# mixer_board_smd.net
KiCad netlist of a schematic drawn in EAGLE
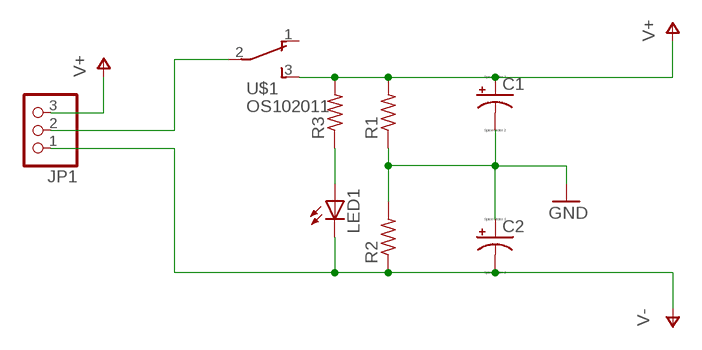
[diagram p0: schematic, sheet 1, part 1 of 2]
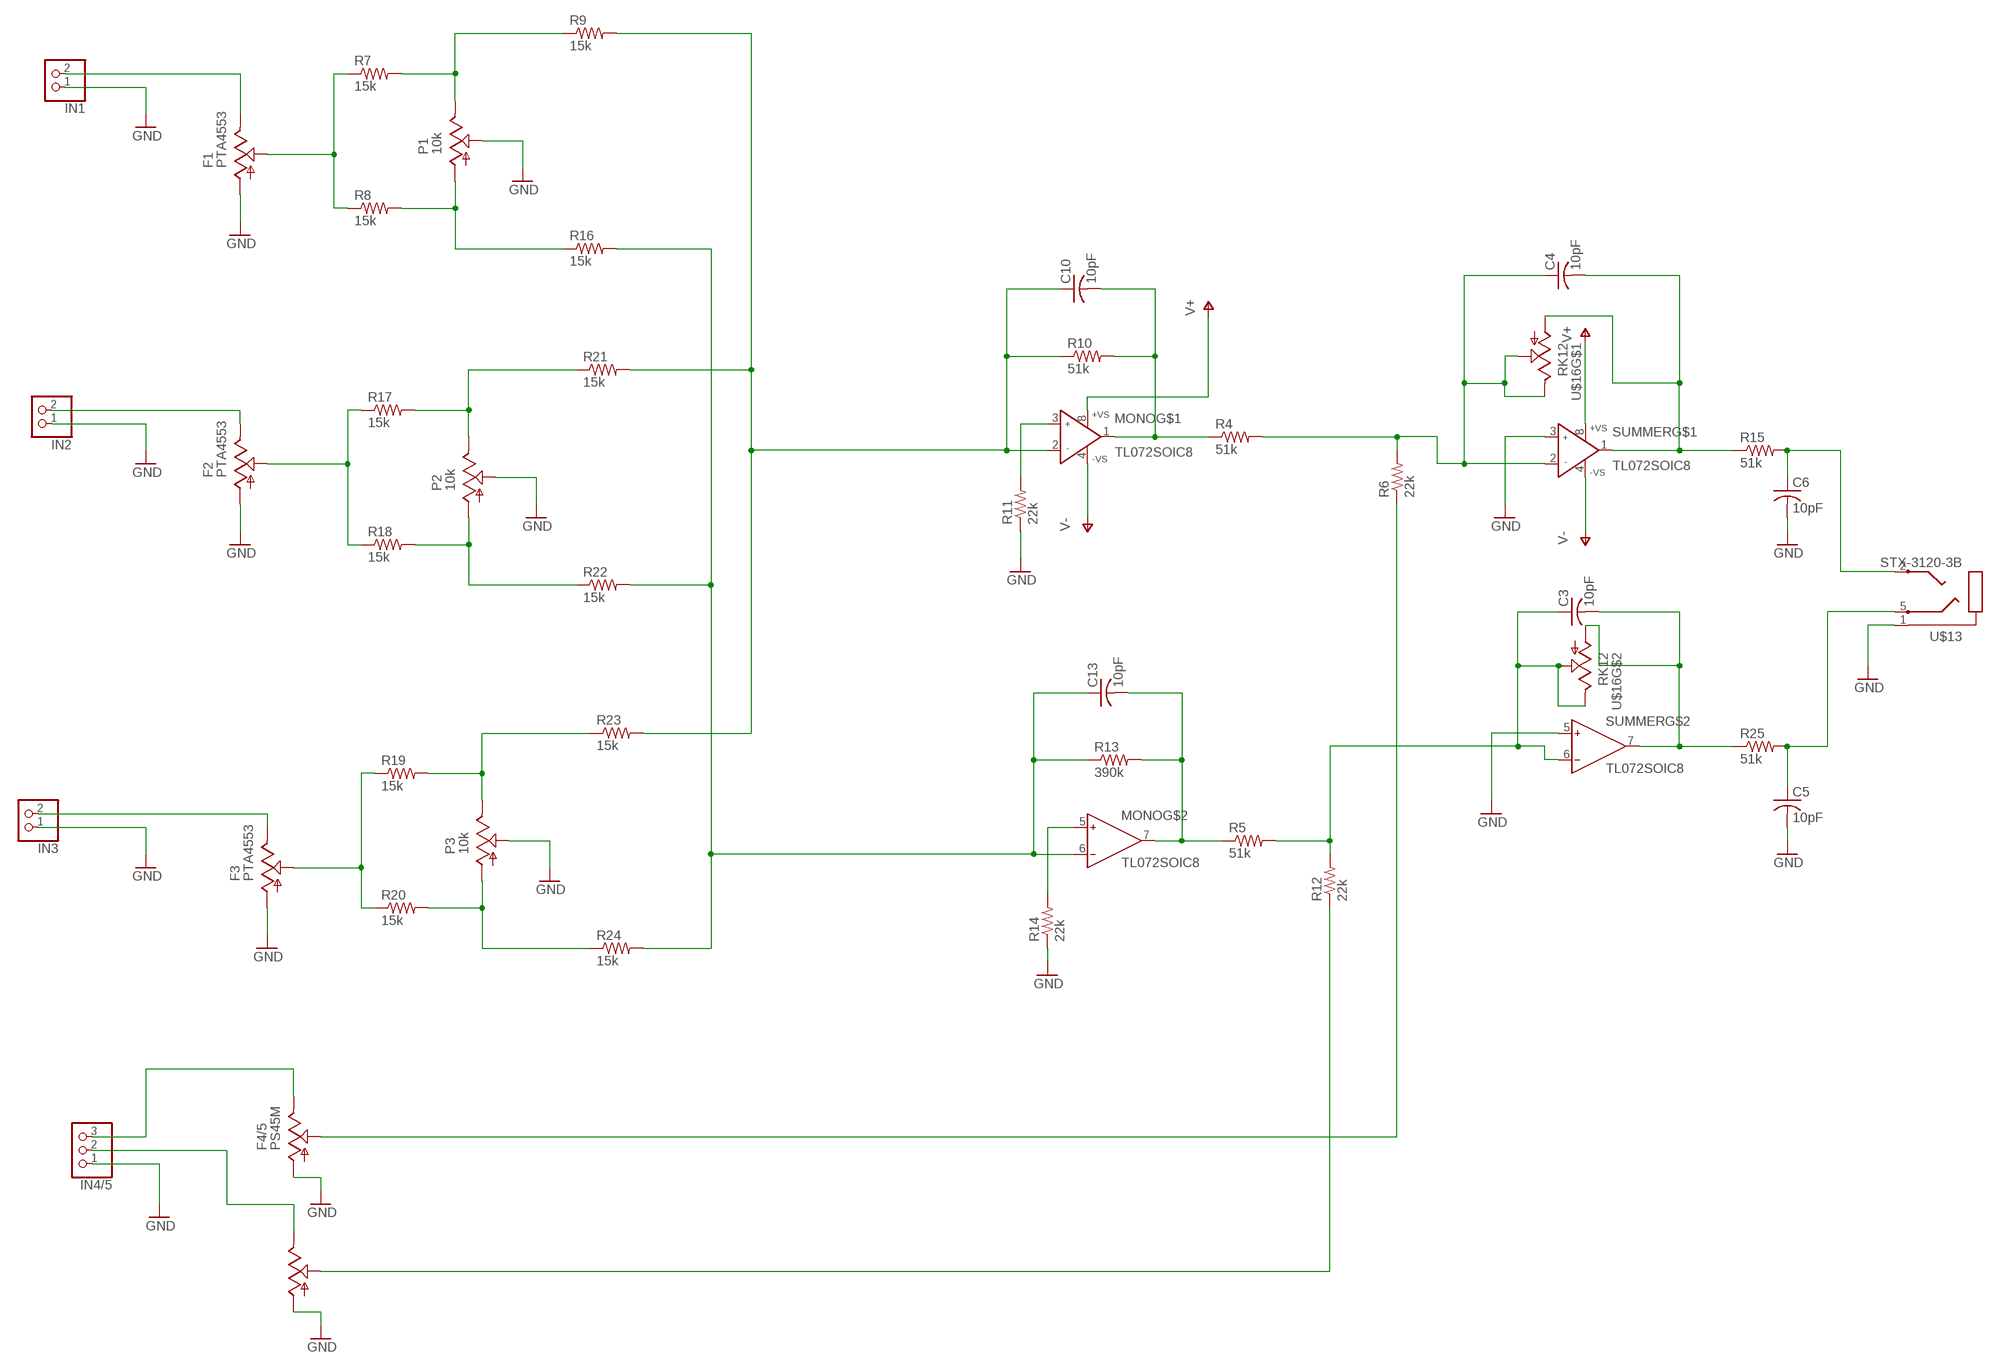
[diagram p1: schematic, sheet 1, part 2 of 2]

(export (version "E")
  (design (tool "Eeschema 10.0.6"))
  (components
    (comp (ref "C1")
      (value "CPOL-USE1.8-4")
      (footprint "eagle-import:E1,8-4")
      (libsource (lib "eagle-import") (part "CPOL-USE1.8-4"))
    )
    (comp (ref "C2")
      (value "CPOL-USE1.8-4")
      (footprint "eagle-import:E1,8-4")
      (libsource (lib "eagle-import") (part "CPOL-USE1.8-4"))
    )
    (comp (ref "C3")
      (value "10pF")
      (footprint "eagle-import:C0805")
      (libsource (lib "eagle-import") (part "C-USC0805"))
    )
    (comp (ref "C4")
      (value "10pF")
      (footprint "eagle-import:C0805")
      (libsource (lib "eagle-import") (part "C-USC0805"))
    )
    (comp (ref "C5")
      (value "10pF")
      (footprint "eagle-import:C0805")
      (libsource (lib "eagle-import") (part "C-USC0805"))
    )
    (comp (ref "C6")
      (value "10pF")
      (footprint "eagle-import:C0805")
      (libsource (lib "eagle-import") (part "C-USC0805"))
    )
    (comp (ref "C10")
      (value "10pF")
      (footprint "eagle-import:C0805")
      (libsource (lib "eagle-import") (part "C-USC0805"))
    )
    (comp (ref "C13")
      (value "10pF")
      (footprint "eagle-import:C0805")
      (libsource (lib "eagle-import") (part "C-USC0805"))
    )
    (comp (ref "F1")
      (value "PTA4553")
      (footprint "eagle-import:PTA4553")
      (libsource (lib "eagle-import") (part "PTA4553"))
    )
    (comp (ref "F2")
      (value "PTA4553")
      (footprint "eagle-import:PTA4553")
      (libsource (lib "eagle-import") (part "PTA4553"))
    )
    (comp (ref "F3")
      (value "PTA4553")
      (footprint "eagle-import:PTA4553")
      (libsource (lib "eagle-import") (part "PTA4553"))
    )
    (comp (ref "F4/5")
      (value "PS45M")
      (footprint "eagle-import:PS45M")
      (libsource (lib "eagle-import") (part "PS45M"))
    )
    (comp (ref "IN1")
      (value "PINHD-1X2/90")
      (footprint "eagle-import:1X02_90")
      (libsource (lib "eagle-import") (part "PINHD-1X2/90"))
    )
    (comp (ref "IN2")
      (value "PINHD-1X2/90")
      (footprint "eagle-import:1X02_90")
      (libsource (lib "eagle-import") (part "PINHD-1X2/90"))
    )
    (comp (ref "IN3")
      (value "PINHD-1X2/90")
      (footprint "eagle-import:1X02_90")
      (libsource (lib "eagle-import") (part "PINHD-1X2/90"))
    )
    (comp (ref "IN4/5")
      (value "PINHD-1X3/90")
      (footprint "eagle-import:1X03_90")
      (libsource (lib "eagle-import") (part "PINHD-1X3/90"))
    )
    (comp (ref "JP1")
      (value "PINHD-1X3/90")
      (footprint "eagle-import:1X03_90")
      (libsource (lib "eagle-import") (part "PINHD-1X3/90"))
    )
    (comp (ref "LED1")
      (value "LEDCHIPLED_1206")
      (footprint "eagle-import:CHIPLED_1206")
      (libsource (lib "eagle-import") (part "LEDCHIPLED_1206"))
    )
    (comp (ref "MONO")
      (value "TL072SOIC8")
      (footprint "eagle-import:SOIC8")
      (libsource (lib "eagle-import") (part "TL072SOIC8"))
    )
    (comp (ref "P1")
      (value "10k")
      (footprint "eagle-import:PTV09A")
      (libsource (lib "eagle-import") (part "PTV09A"))
    )
    (comp (ref "P2")
      (value "10k")
      (footprint "eagle-import:PTV09A")
      (libsource (lib "eagle-import") (part "PTV09A"))
    )
    (comp (ref "P3")
      (value "10k")
      (footprint "eagle-import:PTV09A")
      (libsource (lib "eagle-import") (part "PTV09A"))
    )
    (comp (ref "R1")
      (value "R-US_M0805")
      (footprint "eagle-import:M0805")
      (libsource (lib "eagle-import") (part "R-US_M0805"))
    )
    (comp (ref "R2")
      (value "R-US_M0805")
      (footprint "eagle-import:M0805")
      (libsource (lib "eagle-import") (part "R-US_M0805"))
    )
    (comp (ref "R3")
      (value "R-US_R0805")
      (footprint "eagle-import:R0805")
      (libsource (lib "eagle-import") (part "R-US_R0805"))
    )
    (comp (ref "R4")
      (value "51k")
      (footprint "eagle-import:M0805")
      (libsource (lib "eagle-import") (part "R-US_M0805"))
    )
    (comp (ref "R5")
      (value "51k")
      (footprint "eagle-import:M0805")
      (libsource (lib "eagle-import") (part "R-US_M0805"))
    )
    (comp (ref "R6")
      (value "22k")
      (footprint "eagle-import:M0805")
      (libsource (lib "eagle-import") (part "R-US_M0805"))
    )
    (comp (ref "R7")
      (value "15k")
      (footprint "eagle-import:M0805")
      (libsource (lib "eagle-import") (part "R-US_M0805"))
    )
    (comp (ref "R8")
      (value "15k")
      (footprint "eagle-import:M0805")
      (libsource (lib "eagle-import") (part "R-US_M0805"))
    )
    (comp (ref "R9")
      (value "15k")
      (footprint "eagle-import:M0805")
      (libsource (lib "eagle-import") (part "R-US_M0805"))
    )
    (comp (ref "R10")
      (value "51k")
      (footprint "eagle-import:M0805")
      (libsource (lib "eagle-import") (part "R-US_M0805"))
    )
    (comp (ref "R11")
      (value "22k")
      (footprint "eagle-import:M0805")
      (libsource (lib "eagle-import") (part "R-US_M0805"))
    )
    (comp (ref "R12")
      (value "22k")
      (footprint "eagle-import:M0805")
      (libsource (lib "eagle-import") (part "R-US_M0805"))
    )
    (comp (ref "R13")
      (value "390k")
      (footprint "eagle-import:M0805")
      (libsource (lib "eagle-import") (part "R-US_M0805"))
    )
    (comp (ref "R14")
      (value "22k")
      (footprint "eagle-import:M0805")
      (libsource (lib "eagle-import") (part "R-US_M0805"))
    )
    (comp (ref "R15")
      (value "51k")
      (footprint "eagle-import:M0805")
      (libsource (lib "eagle-import") (part "R-US_M0805"))
    )
    (comp (ref "R16")
      (value "15k")
      (footprint "eagle-import:M0805")
      (libsource (lib "eagle-import") (part "R-US_M0805"))
    )
    (comp (ref "R17")
      (value "15k")
      (footprint "eagle-import:M0805")
      (libsource (lib "eagle-import") (part "R-US_M0805"))
    )
    (comp (ref "R18")
      (value "15k")
      (footprint "eagle-import:M0805")
      (libsource (lib "eagle-import") (part "R-US_M0805"))
    )
    (comp (ref "R19")
      (value "15k")
      (footprint "eagle-import:M0805")
      (libsource (lib "eagle-import") (part "R-US_M0805"))
    )
    (comp (ref "R20")
      (value "15k")
      (footprint "eagle-import:M0805")
      (libsource (lib "eagle-import") (part "R-US_M0805"))
    )
    (comp (ref "R21")
      (value "15k")
      (footprint "eagle-import:M0805")
      (libsource (lib "eagle-import") (part "R-US_M0805"))
    )
    (comp (ref "R22")
      (value "15k")
      (footprint "eagle-import:M0805")
      (libsource (lib "eagle-import") (part "R-US_M0805"))
    )
    (comp (ref "R23")
      (value "15k")
      (footprint "eagle-import:M0805")
      (libsource (lib "eagle-import") (part "R-US_M0805"))
    )
    (comp (ref "R24")
      (value "15k")
      (footprint "eagle-import:M0805")
      (libsource (lib "eagle-import") (part "R-US_M0805"))
    )
    (comp (ref "R25")
      (value "51k")
      (footprint "eagle-import:M0805")
      (libsource (lib "eagle-import") (part "R-US_M0805"))
    )
    (comp (ref "SUMMER")
      (value "TL072SOIC8")
      (footprint "eagle-import:SOIC8")
      (libsource (lib "eagle-import") (part "TL072SOIC8"))
    )
    (comp (ref "U$1")
      (value "OS102011")
      (footprint "eagle-import:OS102011")
      (libsource (lib "eagle-import") (part "OS102011"))
    )
    (comp (ref "U$13")
      (value "STX-3120-3B")
      (footprint "eagle-import:STX-3120")
      (libsource (lib "eagle-import") (part "STX-3120-3B"))
    )
    (comp (ref "U$16")
      (value "RK12")
      (footprint "eagle-import:RK12")
      (libsource (lib "eagle-import") (part "RK12"))
    )
  )
  (nets
    (net (code "1") (name "GND") (class "Default")
      (node (ref "C1") (pin "-") (pinfunction "-_-") (pintype "passive"))
      (node (ref "C2") (pin "+") (pinfunction "+_+") (pintype "passive"))
      (node (ref "C5") (pin "2") (pinfunction "2_2") (pintype "passive"))
      (node (ref "C6") (pin "2") (pinfunction "2_2") (pintype "passive"))
      (node (ref "F1") (pin "1") (pinfunction "1_1") (pintype "passive"))
      (node (ref "F2") (pin "1") (pinfunction "1_1") (pintype "passive"))
      (node (ref "F3") (pin "1") (pinfunction "1_1") (pintype "passive"))
      (node (ref "F4/5") (pin "1") (pinfunction "1_1") (pintype "passive"))
      (node (ref "F4/5") (pin "1'") (pinfunction "1'_1'") (pintype "passive"))
      (node (ref "IN1") (pin "1") (pinfunction "1_1") (pintype "passive"))
      (node (ref "IN2") (pin "1") (pinfunction "1_1") (pintype "passive"))
      (node (ref "IN3") (pin "1") (pinfunction "1_1") (pintype "passive"))
      (node (ref "IN4/5") (pin "1") (pinfunction "1_1") (pintype "passive"))
      (node (ref "P1") (pin "2") (pinfunction "2_2") (pintype "passive"))
      (node (ref "P2") (pin "2") (pinfunction "2_2") (pintype "passive"))
      (node (ref "P3") (pin "2") (pinfunction "2_2") (pintype "passive"))
      (node (ref "R1") (pin "1") (pinfunction "1_1") (pintype "passive"))
      (node (ref "R11") (pin "1") (pinfunction "1_1") (pintype "passive"))
      (node (ref "R14") (pin "1") (pinfunction "1_1") (pintype "passive"))
      (node (ref "R2") (pin "2") (pinfunction "2_2") (pintype "passive"))
      (node (ref "SUMMER") (pin "3") (pinfunction "IN+_3") (pintype "input"))
      (node (ref "SUMMER") (pin "5") (pinfunction "IN+_5") (pintype "input"))
      (node (ref "U$13") (pin "1") (pinfunction "1_1") (pintype "passive"))
    )
    (net (code "2") (name "Net-(C5-Pad1)") (class "Default")
      (node (ref "C5") (pin "1") (pinfunction "1_1") (pintype "passive"))
      (node (ref "R25") (pin "2") (pinfunction "2_2") (pintype "passive"))
      (node (ref "U$13") (pin "5") (pinfunction "5_5") (pintype "passive"))
    )
    (net (code "3") (name "Net-(C6-Pad1)") (class "Default")
      (node (ref "C6") (pin "1") (pinfunction "1_1") (pintype "passive"))
      (node (ref "R15") (pin "2") (pinfunction "2_2") (pintype "passive"))
      (node (ref "U$13") (pin "2") (pinfunction "2_2") (pintype "passive"))
    )
    (net (code "4") (name "Net-(F1-Pad2)") (class "Default")
      (node (ref "F1") (pin "2") (pinfunction "2_2") (pintype "passive"))
      (node (ref "R7") (pin "1") (pinfunction "1_1") (pintype "passive"))
      (node (ref "R8") (pin "1") (pinfunction "1_1") (pintype "passive"))
    )
    (net (code "5") (name "Net-(F1-Pad3)") (class "Default")
      (node (ref "F1") (pin "3") (pinfunction "3_3") (pintype "passive"))
      (node (ref "IN1") (pin "2") (pinfunction "2_2") (pintype "passive"))
    )
    (net (code "6") (name "Net-(F2-Pad2)") (class "Default")
      (node (ref "F2") (pin "2") (pinfunction "2_2") (pintype "passive"))
      (node (ref "R17") (pin "1") (pinfunction "1_1") (pintype "passive"))
      (node (ref "R18") (pin "1") (pinfunction "1_1") (pintype "passive"))
    )
    (net (code "7") (name "Net-(F2-Pad3)") (class "Default")
      (node (ref "F2") (pin "3") (pinfunction "3_3") (pintype "passive"))
      (node (ref "IN2") (pin "2") (pinfunction "2_2") (pintype "passive"))
    )
    (net (code "8") (name "Net-(F3-Pad2)") (class "Default")
      (node (ref "F3") (pin "2") (pinfunction "2_2") (pintype "passive"))
      (node (ref "R19") (pin "1") (pinfunction "1_1") (pintype "passive"))
      (node (ref "R20") (pin "1") (pinfunction "1_1") (pintype "passive"))
    )
    (net (code "9") (name "Net-(F3-Pad3)") (class "Default")
      (node (ref "F3") (pin "3") (pinfunction "3_3") (pintype "passive"))
      (node (ref "IN3") (pin "2") (pinfunction "2_2") (pintype "passive"))
    )
    (net (code "10") (name "Net-(F4/5-Pad2')") (class "Default")
      (node (ref "F4/5") (pin "2'") (pinfunction "2'_2'") (pintype "passive"))
      (node (ref "R12") (pin "1") (pinfunction "1_1") (pintype "passive"))
    )
    (net (code "11") (name "Net-(F4/5-Pad2)") (class "Default")
      (node (ref "F4/5") (pin "2") (pinfunction "2_2") (pintype "passive"))
      (node (ref "R6") (pin "1") (pinfunction "1_1") (pintype "passive"))
    )
    (net (code "12") (name "Net-(F4/5-Pad3')") (class "Default")
      (node (ref "F4/5") (pin "3'") (pinfunction "3'_3'") (pintype "passive"))
      (node (ref "IN4/5") (pin "2") (pinfunction "2_2") (pintype "passive"))
    )
    (net (code "13") (name "Net-(F4/5-Pad3)") (class "Default")
      (node (ref "F4/5") (pin "3") (pinfunction "3_3") (pintype "passive"))
      (node (ref "IN4/5") (pin "3") (pinfunction "3_3") (pintype "passive"))
    )
    (net (code "14") (name "Net-(LED1-PadA)") (class "Default")
      (node (ref "LED1") (pin "A") (pinfunction "A_A") (pintype "passive"))
      (node (ref "R3") (pin "1") (pinfunction "1_1") (pintype "passive"))
    )
    (net (code "15") (name "Net-(MONOA-IN+)") (class "Default")
      (node (ref "MONO") (pin "3") (pinfunction "IN+_3") (pintype "input"))
      (node (ref "R11") (pin "2") (pinfunction "2_2") (pintype "passive"))
    )
    (net (code "16") (name "Net-(MONOA-IN-)") (class "Default")
      (node (ref "C10") (pin "1") (pinfunction "1_1") (pintype "passive"))
      (node (ref "MONO") (pin "2") (pinfunction "IN-_2") (pintype "input"))
      (node (ref "R10") (pin "1") (pinfunction "1_1") (pintype "passive"))
      (node (ref "R21") (pin "2") (pinfunction "2_2") (pintype "passive"))
      (node (ref "R23") (pin "2") (pinfunction "2_2") (pintype "passive"))
      (node (ref "R9") (pin "2") (pinfunction "2_2") (pintype "passive"))
    )
    (net (code "17") (name "Net-(MONOA-OUT)") (class "Default")
      (node (ref "C10") (pin "2") (pinfunction "2_2") (pintype "passive"))
      (node (ref "MONO") (pin "1") (pinfunction "OUT_1") (pintype "output"))
      (node (ref "R10") (pin "2") (pinfunction "2_2") (pintype "passive"))
      (node (ref "R4") (pin "1") (pinfunction "1_1") (pintype "passive"))
    )
    (net (code "18") (name "Net-(MONOB-IN+)") (class "Default")
      (node (ref "MONO") (pin "5") (pinfunction "IN+_5") (pintype "input"))
      (node (ref "R14") (pin "2") (pinfunction "2_2") (pintype "passive"))
    )
    (net (code "19") (name "Net-(MONOB-IN-)") (class "Default")
      (node (ref "C13") (pin "1") (pinfunction "1_1") (pintype "passive"))
      (node (ref "MONO") (pin "6") (pinfunction "IN-_6") (pintype "input"))
      (node (ref "R13") (pin "1") (pinfunction "1_1") (pintype "passive"))
      (node (ref "R16") (pin "2") (pinfunction "2_2") (pintype "passive"))
      (node (ref "R22") (pin "2") (pinfunction "2_2") (pintype "passive"))
      (node (ref "R24") (pin "2") (pinfunction "2_2") (pintype "passive"))
    )
    (net (code "20") (name "Net-(MONOB-OUT)") (class "Default")
      (node (ref "C13") (pin "2") (pinfunction "2_2") (pintype "passive"))
      (node (ref "MONO") (pin "7") (pinfunction "OUT_7") (pintype "output"))
      (node (ref "R13") (pin "2") (pinfunction "2_2") (pintype "passive"))
      (node (ref "R5") (pin "1") (pinfunction "1_1") (pintype "passive"))
    )
    (net (code "21") (name "Net-(P1-Pad1)") (class "Default")
      (node (ref "P1") (pin "1") (pinfunction "1_1") (pintype "passive"))
      (node (ref "R16") (pin "1") (pinfunction "1_1") (pintype "passive"))
      (node (ref "R8") (pin "2") (pinfunction "2_2") (pintype "passive"))
    )
    (net (code "22") (name "Net-(P1-Pad3)") (class "Default")
      (node (ref "P1") (pin "3") (pinfunction "3_3") (pintype "passive"))
      (node (ref "R7") (pin "2") (pinfunction "2_2") (pintype "passive"))
      (node (ref "R9") (pin "1") (pinfunction "1_1") (pintype "passive"))
    )
    (net (code "23") (name "Net-(P2-Pad1)") (class "Default")
      (node (ref "P2") (pin "1") (pinfunction "1_1") (pintype "passive"))
      (node (ref "R18") (pin "2") (pinfunction "2_2") (pintype "passive"))
      (node (ref "R22") (pin "1") (pinfunction "1_1") (pintype "passive"))
    )
    (net (code "24") (name "Net-(P2-Pad3)") (class "Default")
      (node (ref "P2") (pin "3") (pinfunction "3_3") (pintype "passive"))
      (node (ref "R17") (pin "2") (pinfunction "2_2") (pintype "passive"))
      (node (ref "R21") (pin "1") (pinfunction "1_1") (pintype "passive"))
    )
    (net (code "25") (name "Net-(P3-Pad1)") (class "Default")
      (node (ref "P3") (pin "1") (pinfunction "1_1") (pintype "passive"))
      (node (ref "R20") (pin "2") (pinfunction "2_2") (pintype "passive"))
      (node (ref "R24") (pin "1") (pinfunction "1_1") (pintype "passive"))
    )
    (net (code "26") (name "Net-(P3-Pad3)") (class "Default")
      (node (ref "P3") (pin "3") (pinfunction "3_3") (pintype "passive"))
      (node (ref "R19") (pin "2") (pinfunction "2_2") (pintype "passive"))
      (node (ref "R23") (pin "1") (pinfunction "1_1") (pintype "passive"))
    )
    (net (code "27") (name "Net-(SUMMERA-IN-)") (class "Default")
      (node (ref "C4") (pin "1") (pinfunction "1_1") (pintype "passive"))
      (node (ref "R4") (pin "2") (pinfunction "2_2") (pintype "passive"))
      (node (ref "R6") (pin "2") (pinfunction "2_2") (pintype "passive"))
      (node (ref "SUMMER") (pin "2") (pinfunction "IN-_2") (pintype "input"))
      (node (ref "U$16") (pin "2") (pinfunction "2_2") (pintype "passive"))
      (node (ref "U$16") (pin "3") (pinfunction "3_3") (pintype "passive"))
    )
    (net (code "28") (name "Net-(SUMMERA-OUT)") (class "Default")
      (node (ref "C4") (pin "2") (pinfunction "2_2") (pintype "passive"))
      (node (ref "R15") (pin "1") (pinfunction "1_1") (pintype "passive"))
      (node (ref "SUMMER") (pin "1") (pinfunction "OUT_1") (pintype "output"))
      (node (ref "U$16") (pin "1") (pinfunction "1_1") (pintype "passive"))
    )
    (net (code "29") (name "Net-(SUMMERB-IN-)") (class "Default")
      (node (ref "C3") (pin "1") (pinfunction "1_1") (pintype "passive"))
      (node (ref "R12") (pin "2") (pinfunction "2_2") (pintype "passive"))
      (node (ref "R5") (pin "2") (pinfunction "2_2") (pintype "passive"))
      (node (ref "SUMMER") (pin "6") (pinfunction "IN-_6") (pintype "input"))
      (node (ref "U$16") (pin "2'") (pinfunction "2_2'") (pintype "passive"))
      (node (ref "U$16") (pin "3'") (pinfunction "3_3'") (pintype "passive"))
    )
    (net (code "30") (name "Net-(SUMMERB-OUT)") (class "Default")
      (node (ref "C3") (pin "2") (pinfunction "2_2") (pintype "passive"))
      (node (ref "R25") (pin "1") (pinfunction "1_1") (pintype "passive"))
      (node (ref "SUMMER") (pin "7") (pinfunction "OUT_7") (pintype "output"))
      (node (ref "U$16") (pin "1'") (pinfunction "1_1'") (pintype "passive"))
    )
    (net (code "31") (name "Net-(U$1-P)") (class "Default")
      (node (ref "JP1") (pin "2") (pinfunction "2_2") (pintype "passive"))
      (node (ref "U$1") (pin "2") (pinfunction "P_2") (pintype "passive"))
    )
    (net (code "32") (name "V+") (class "Default")
      (node (ref "C1") (pin "+") (pinfunction "+_+") (pintype "passive"))
      (node (ref "JP1") (pin "3") (pinfunction "3_3") (pintype "passive"))
      (node (ref "MONO") (pin "8") (pinfunction "+VS_8") (pintype "input"))
      (node (ref "R1") (pin "2") (pinfunction "2_2") (pintype "passive"))
      (node (ref "R3") (pin "2") (pinfunction "2_2") (pintype "passive"))
      (node (ref "SUMMER") (pin "8") (pinfunction "+VS_8") (pintype "input"))
      (node (ref "U$1") (pin "3") (pinfunction "S_3") (pintype "passive"))
    )
    (net (code "33") (name "V-") (class "Default")
      (node (ref "C2") (pin "-") (pinfunction "-_-") (pintype "passive"))
      (node (ref "JP1") (pin "1") (pinfunction "1_1") (pintype "passive"))
      (node (ref "LED1") (pin "C") (pinfunction "C_C") (pintype "passive"))
      (node (ref "MONO") (pin "4") (pinfunction "-VS_4") (pintype "input"))
      (node (ref "R2") (pin "1") (pinfunction "1_1") (pintype "passive"))
      (node (ref "SUMMER") (pin "4") (pinfunction "-VS_4") (pintype "input"))
    )
    (net (code "34") (name "unconnected-(U$1-O-Pad1)") (class "Default")
      (node (ref "U$1") (pin "1") (pinfunction "O_1") (pintype "passive"))
    )
  )
)
